# senseBox-Eye_v1_1.net
KiCad netlist of a schematic drawn in EAGLE
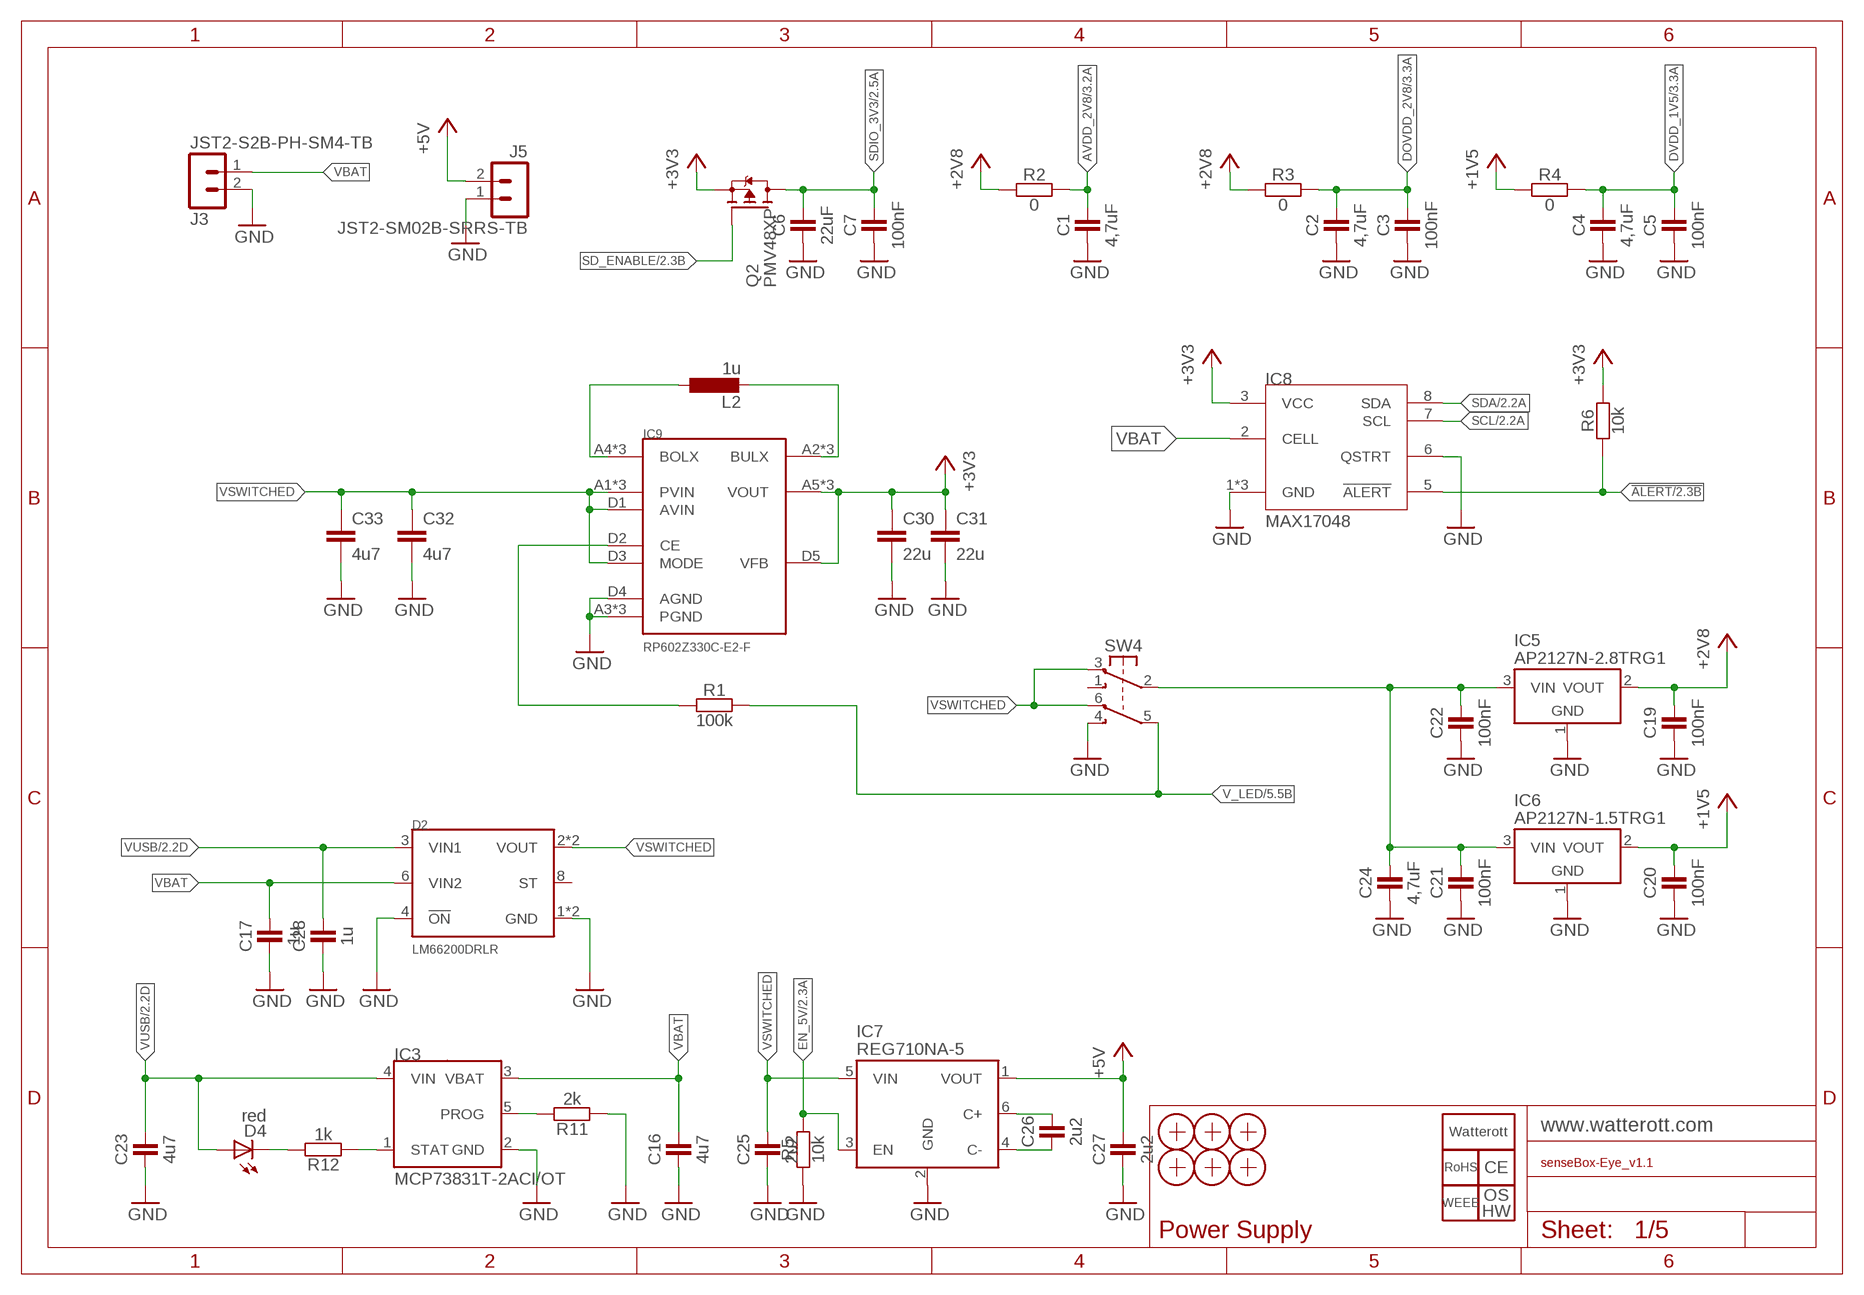
[diagram p0: schematic, sheet 1]
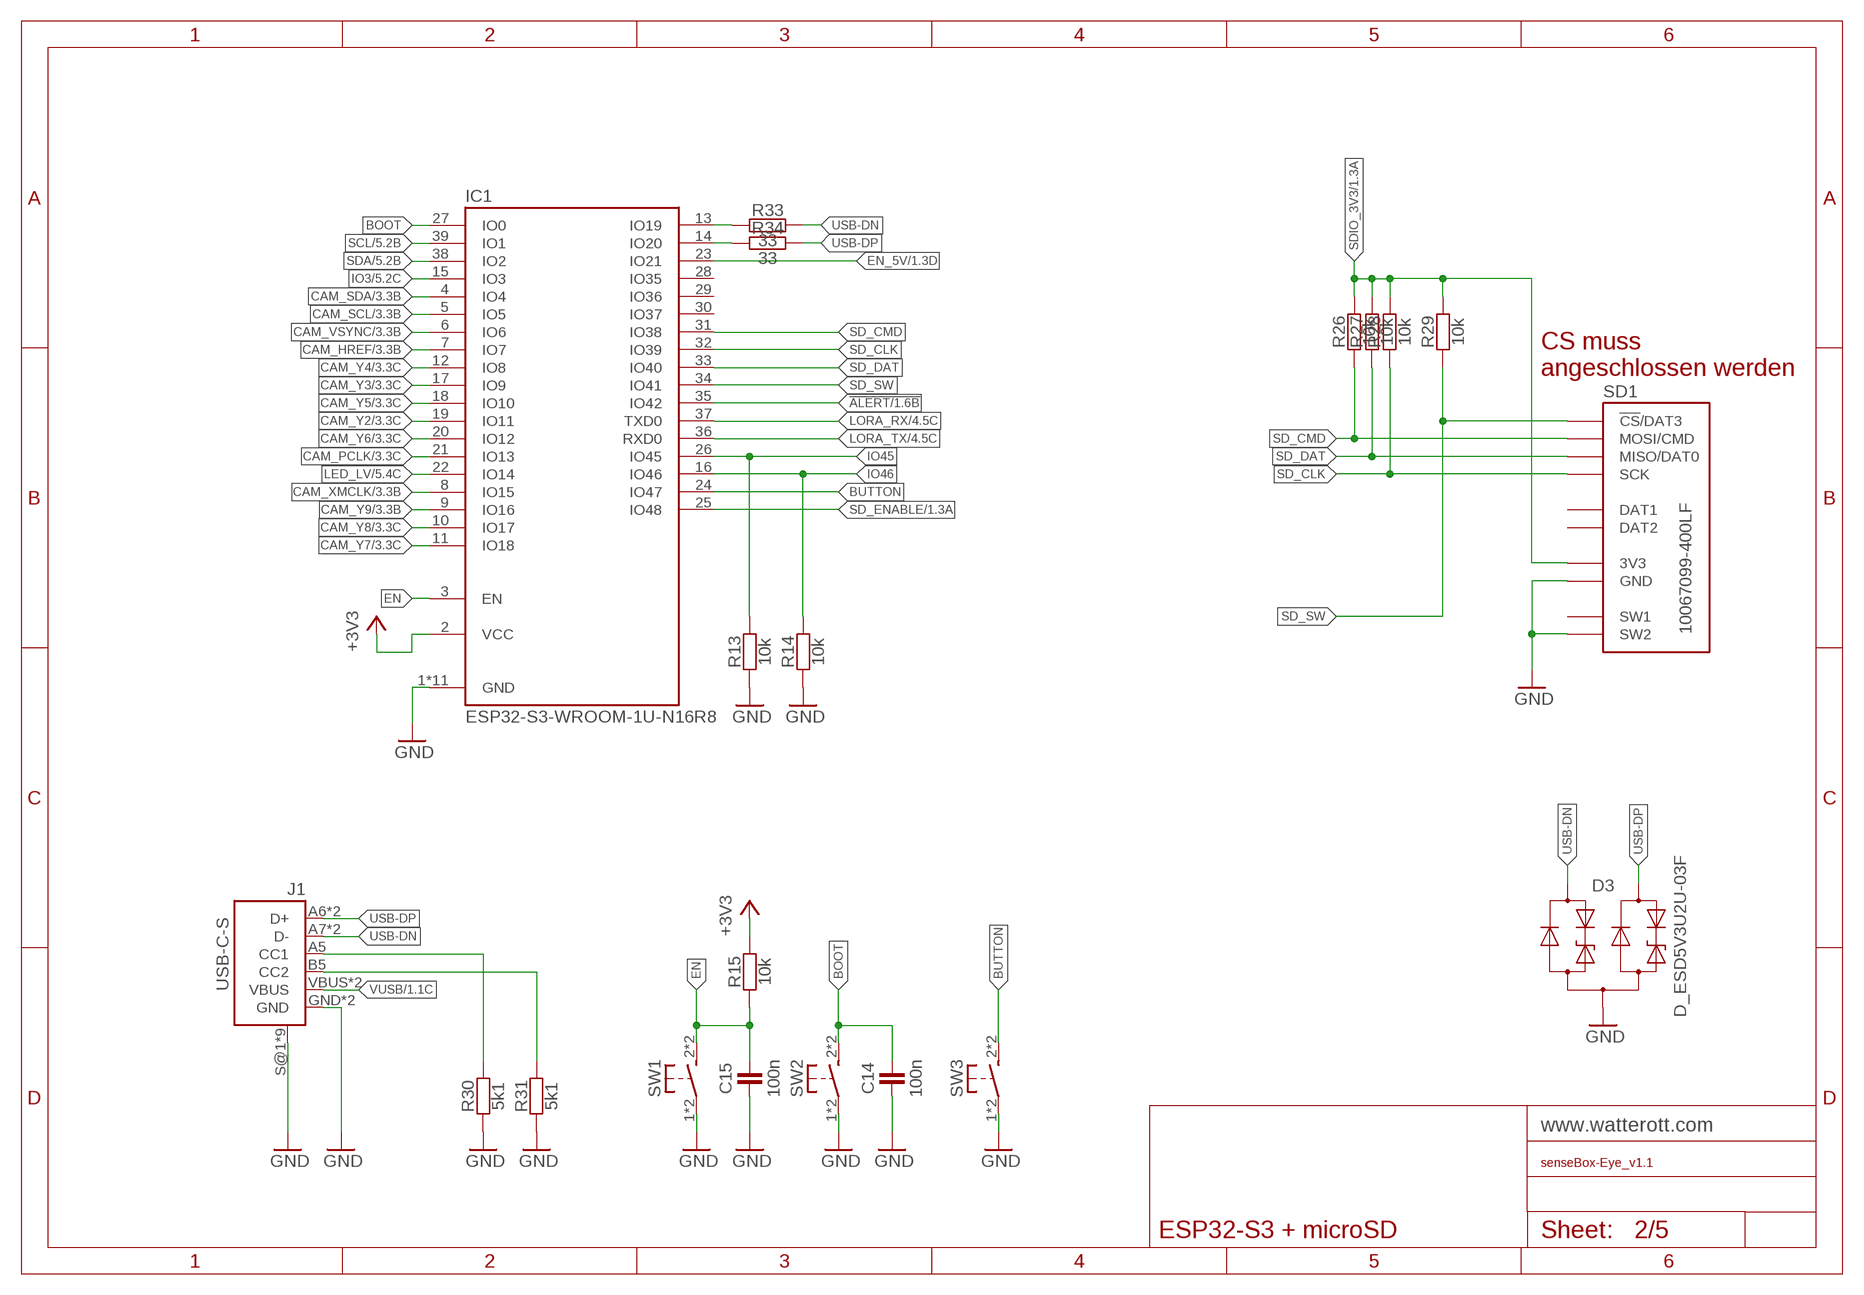
[diagram p1: schematic, sheet 2]
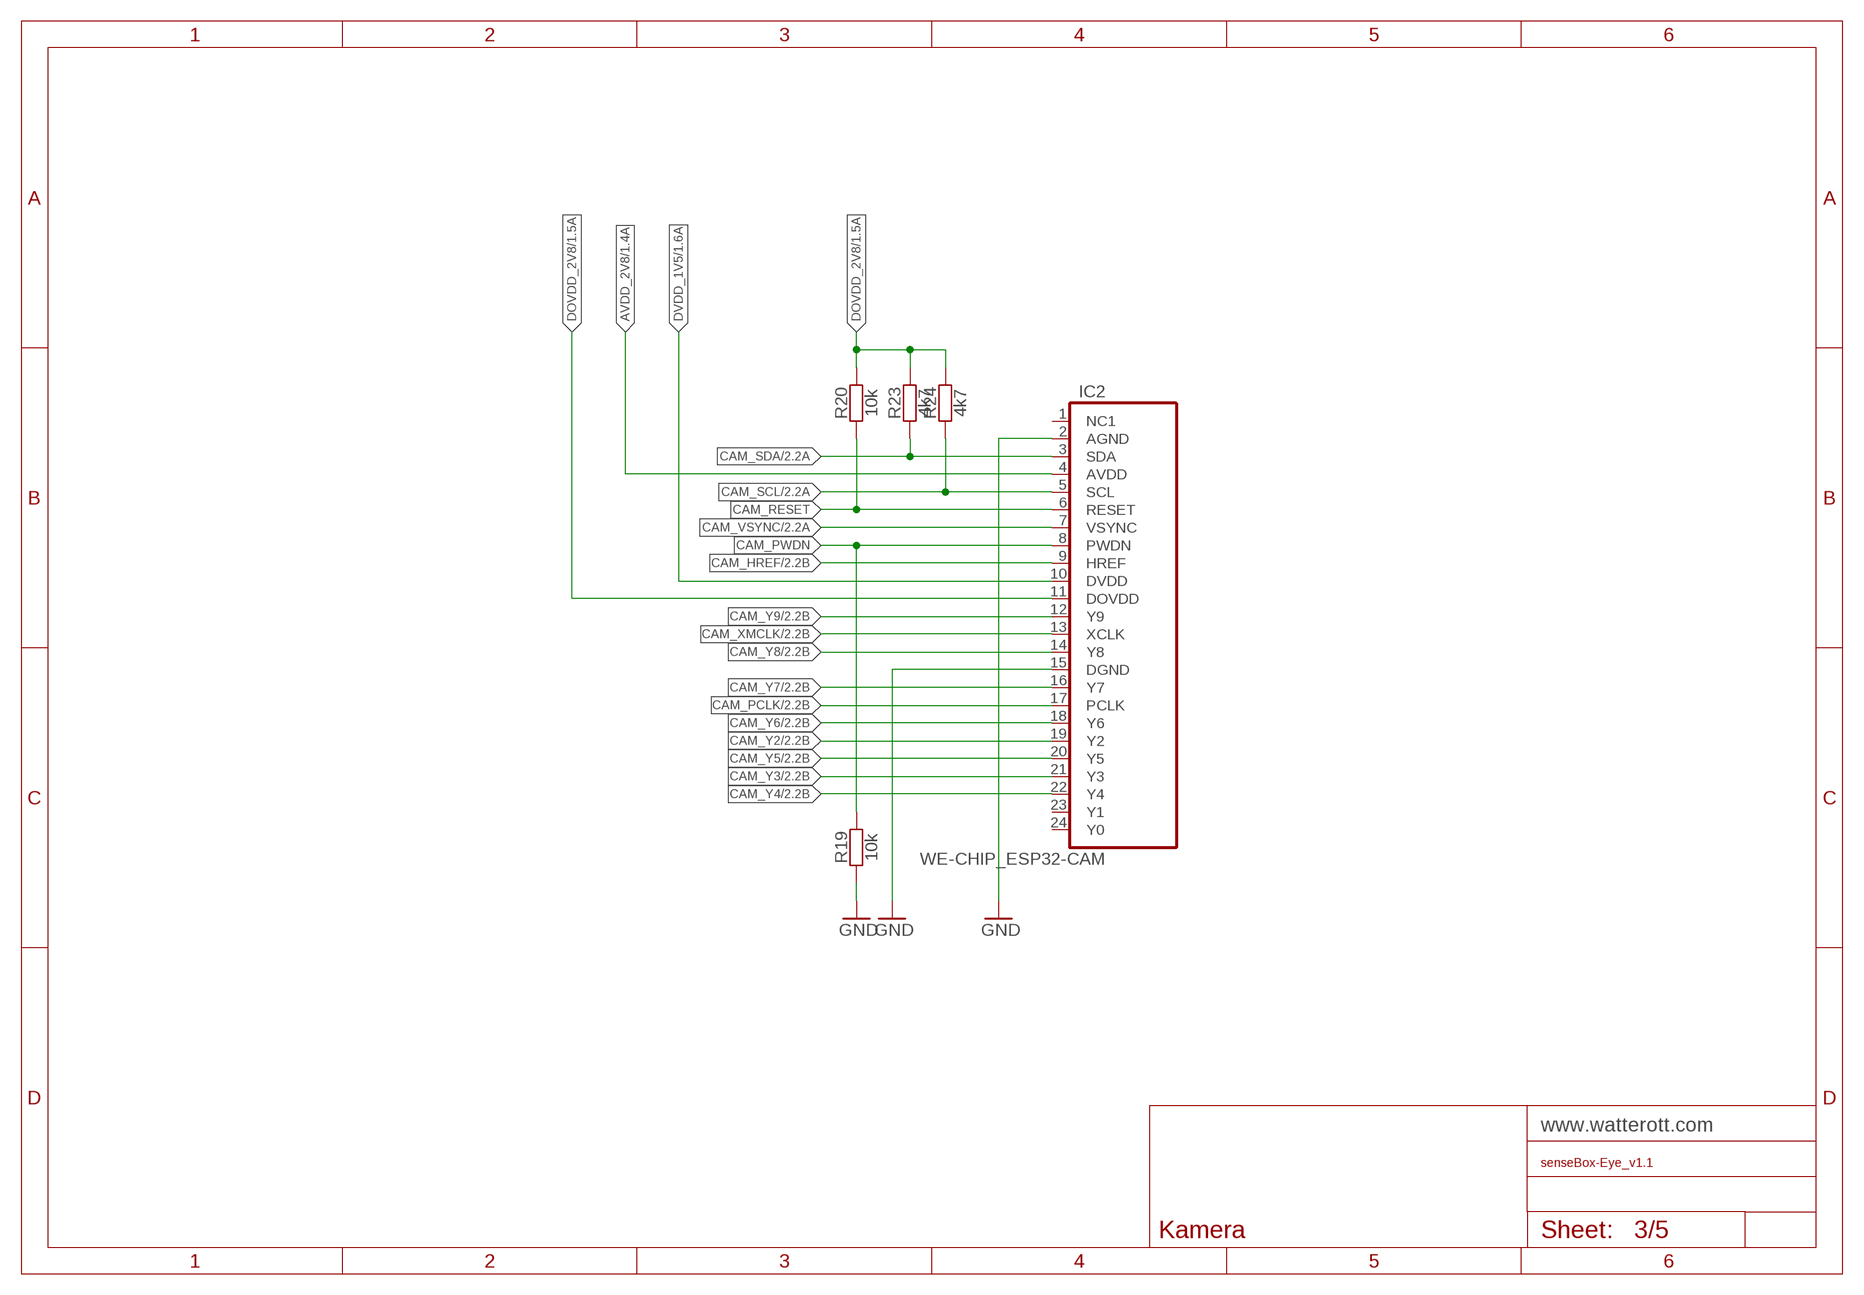
[diagram p2: schematic, sheet 3]
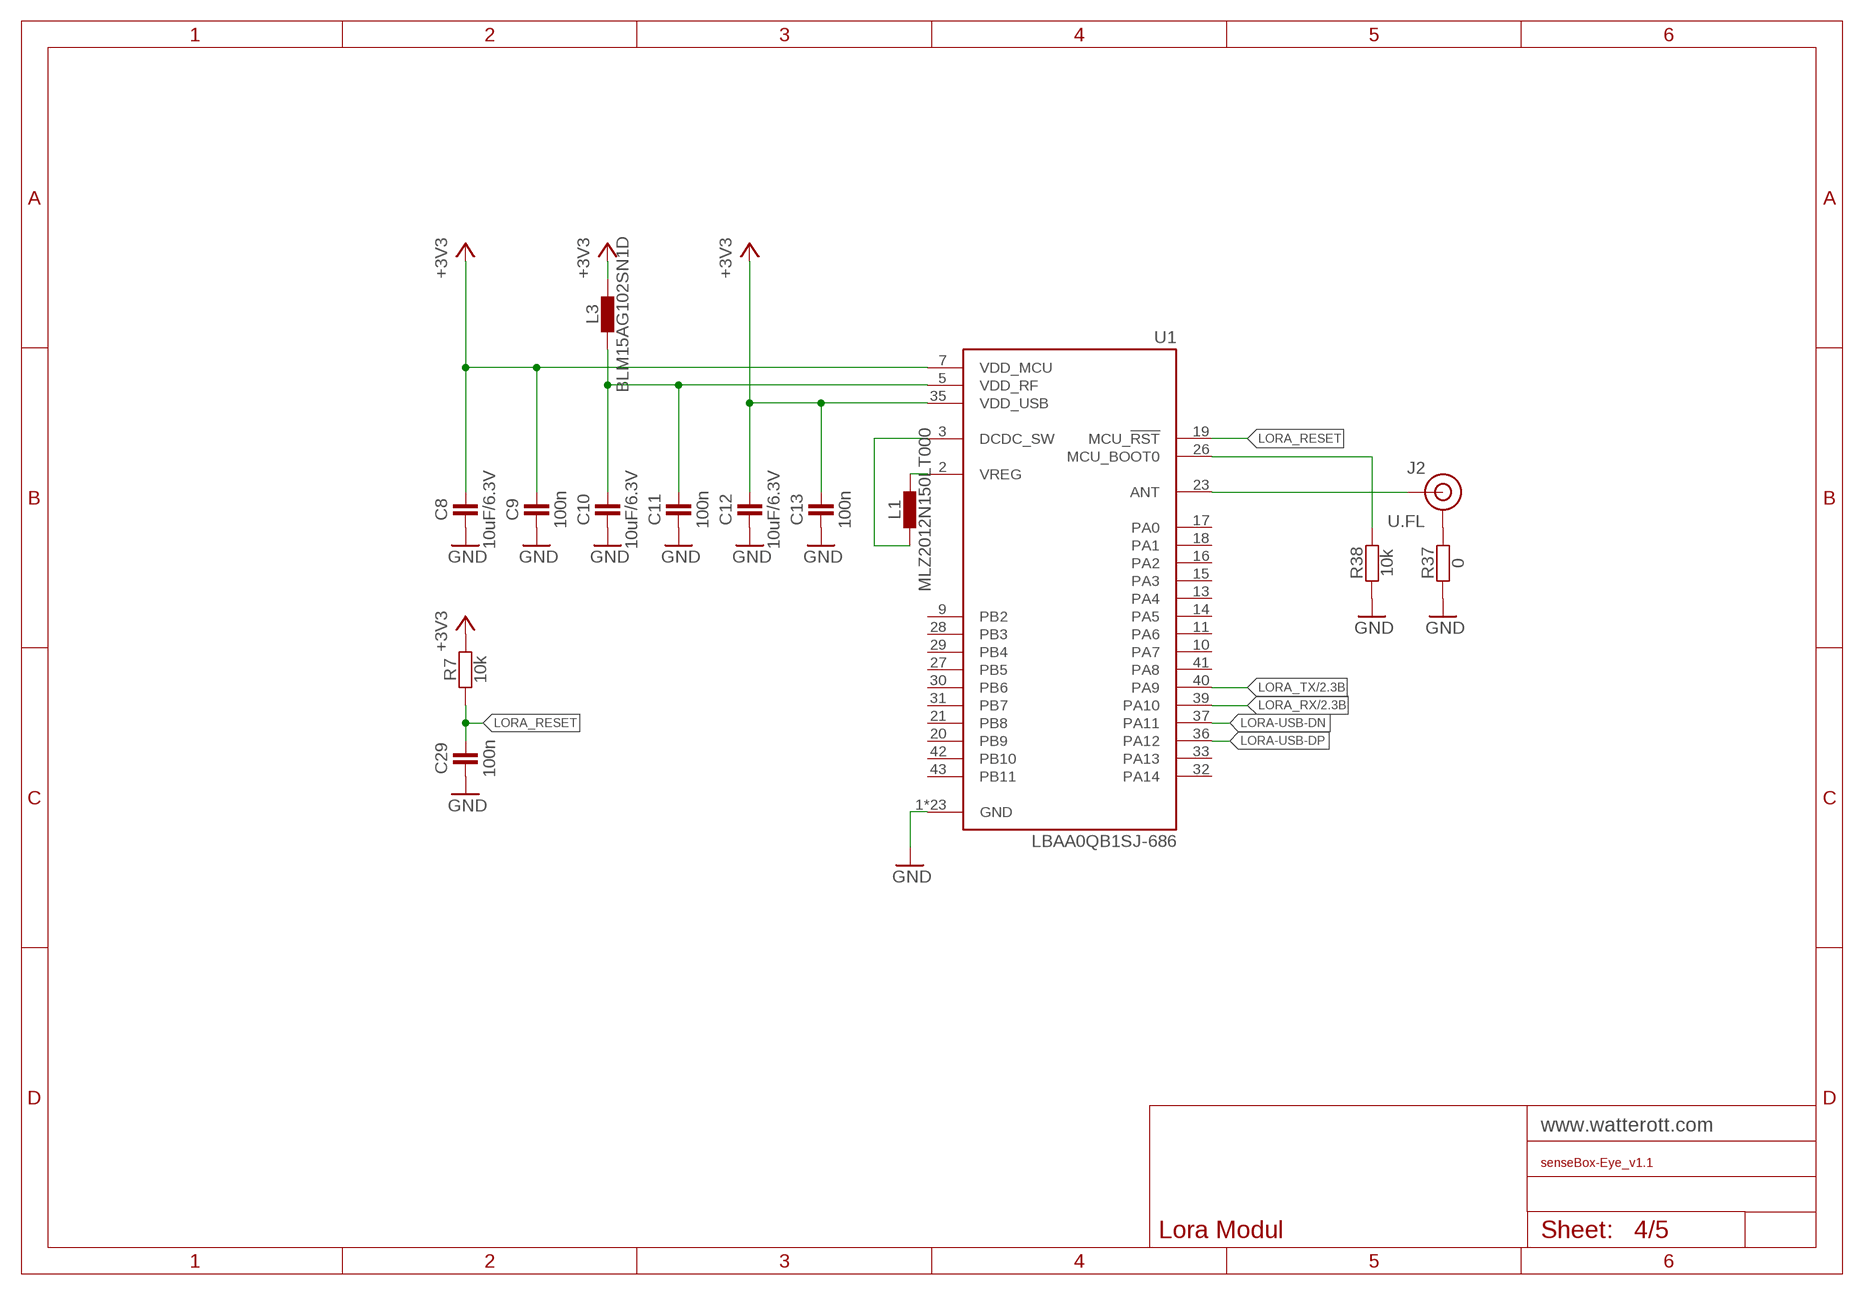
[diagram p3: schematic, sheet 4]
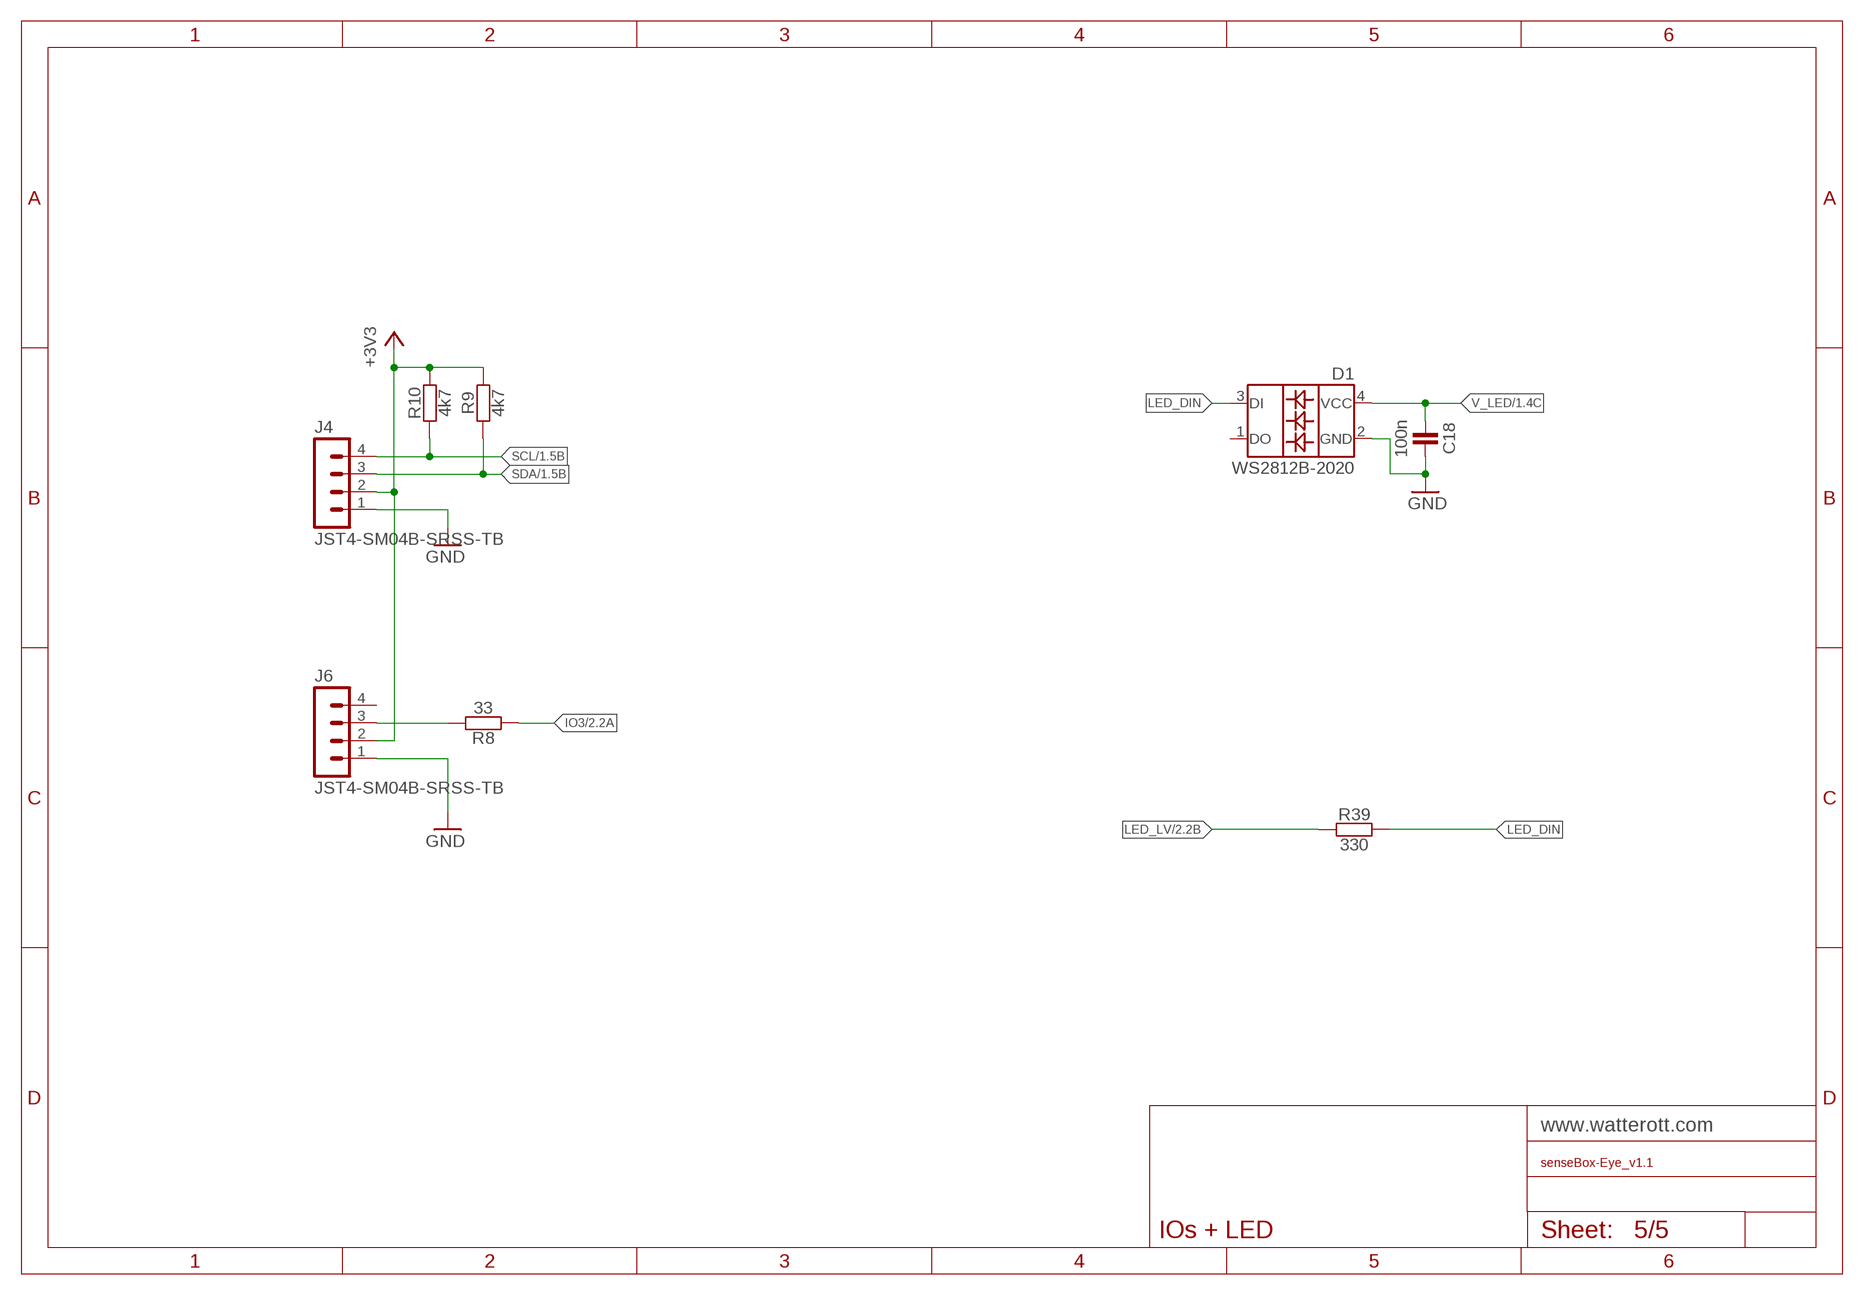
[diagram p4: schematic, sheet 5]

(export (version "E")
  (design (tool "Eeschema 10.0.6"))
  (components
    (comp (ref "C14")
      (value "100n")
      (footprint "eagle-import:C0402")
      (libsource (lib "eagle-import") (part "CAPACITOR-0402"))
    )
    (comp (ref "C15")
      (value "100n")
      (footprint "eagle-import:C0402")
      (libsource (lib "eagle-import") (part "CAPACITOR-0402"))
    )
    (comp (ref "D3")
      (value "D_ESD5V3U2U-03F")
      (footprint "eagle-import:SOT723")
      (libsource (lib "eagle-import") (part "D_ESD5V3U2U-03F"))
    )
    (comp (ref "IC1")
      (value "ESP32-S3-WROOM-1U-N16R8")
      (footprint "eagle-import:ESP32-S3-WROOM-1U")
      (libsource (lib "eagle-import") (part "ESP32_S3-WROOM-1"))
    )
    (comp (ref "J1")
      (value "USB-C-S")
      (footprint "eagle-import:USB-C-S")
      (libsource (lib "eagle-import") (part "USB-C-S"))
    )
    (comp (ref "R13")
      (value "10k")
      (footprint "eagle-import:C0402")
      (libsource (lib "eagle-import") (part "RESISTOR-0402"))
    )
    (comp (ref "R14")
      (value "10k")
      (footprint "eagle-import:C0402")
      (libsource (lib "eagle-import") (part "RESISTOR-0402"))
    )
    (comp (ref "R15")
      (value "10k")
      (footprint "eagle-import:C0402")
      (libsource (lib "eagle-import") (part "RESISTOR-0402"))
    )
    (comp (ref "R26")
      (value "10k")
      (footprint "eagle-import:C0402")
      (libsource (lib "eagle-import") (part "RESISTOR-0402"))
    )
    (comp (ref "R27")
      (value "10k")
      (footprint "eagle-import:C0402")
      (libsource (lib "eagle-import") (part "RESISTOR-0402"))
    )
    (comp (ref "R28")
      (value "10k")
      (footprint "eagle-import:C0402")
      (libsource (lib "eagle-import") (part "RESISTOR-0402"))
    )
    (comp (ref "R29")
      (value "10k")
      (footprint "eagle-import:C0402")
      (libsource (lib "eagle-import") (part "RESISTOR-0402"))
    )
    (comp (ref "R30")
      (value "5k1")
      (footprint "eagle-import:C0402")
      (libsource (lib "eagle-import") (part "RESISTOR-0402"))
    )
    (comp (ref "R31")
      (value "5k1")
      (footprint "eagle-import:C0402")
      (libsource (lib "eagle-import") (part "RESISTOR-0402"))
    )
    (comp (ref "R33")
      (value "33")
      (footprint "eagle-import:C0402")
      (libsource (lib "eagle-import") (part "RESISTOR-0402"))
    )
    (comp (ref "R34")
      (value "33")
      (footprint "eagle-import:C0402")
      (libsource (lib "eagle-import") (part "RESISTOR-0402"))
    )
    (comp (ref "SD1")
      (value "10067099-400LF")
      (footprint "eagle-import:SD_47309XXXX")
      (libsource (lib "eagle-import") (part "SD-CARD-MSD47"))
    )
    (comp (ref "SW1")
      (value "SW-TACTILE-TL3305")
      (footprint "eagle-import:TL3305")
      (libsource (lib "eagle-import") (part "SW-TACTILE-TL3305"))
    )
    (comp (ref "SW2")
      (value "SW-TACTILE-TL3305")
      (footprint "eagle-import:TL3305")
      (libsource (lib "eagle-import") (part "SW-TACTILE-TL3305"))
    )
    (comp (ref "SW3")
      (value "SW-TACTILE-TL3305")
      (footprint "eagle-import:TL3305")
      (libsource (lib "eagle-import") (part "SW-TACTILE-TL3305"))
    )
    (comp (ref "C18")
      (value "100n")
      (footprint "eagle-import:C0402")
      (libsource (lib "eagle-import") (part "CAPACITOR-0402"))
    )
    (comp (ref "D1")
      (value "WS2812B-2020")
      (footprint "eagle-import:WS2812_2020")
      (libsource (lib "eagle-import") (part "WS2812B-2020"))
    )
    (comp (ref "J4")
      (value "JST4-SM04B-SRSS-TB")
      (footprint "eagle-import:JST_SM04B-SRSS-TB")
      (libsource (lib "eagle-import") (part "JST4-SM04B-SRSS-TB"))
    )
    (comp (ref "J6")
      (value "JST4-SM04B-SRSS-TB")
      (footprint "eagle-import:JST_SM04B-SRSS-TB")
      (libsource (lib "eagle-import") (part "JST4-SM04B-SRSS-TB"))
    )
    (comp (ref "R8")
      (value "33")
      (footprint "eagle-import:C0402")
      (libsource (lib "eagle-import") (part "RESISTOR-0402"))
    )
    (comp (ref "R9")
      (value "4k7")
      (footprint "eagle-import:C0402")
      (libsource (lib "eagle-import") (part "RESISTOR-0402"))
    )
    (comp (ref "R10")
      (value "4k7")
      (footprint "eagle-import:C0402")
      (libsource (lib "eagle-import") (part "RESISTOR-0402"))
    )
    (comp (ref "R39")
      (value "330")
      (footprint "eagle-import:C0402")
      (libsource (lib "eagle-import") (part "RESISTOR-0402"))
    )
    (comp (ref "IC2")
      (value "WE-CHIP_ESP32-CAM")
      (footprint "eagle-import:WE-CHIP_FPC24-0.5-CAM")
      (libsource (lib "eagle-import") (part "WE-CHIP_ESP32-CAM"))
    )
    (comp (ref "R19")
      (value "10k")
      (footprint "eagle-import:C0402")
      (libsource (lib "eagle-import") (part "RESISTOR-0402"))
    )
    (comp (ref "R20")
      (value "10k")
      (footprint "eagle-import:C0402")
      (libsource (lib "eagle-import") (part "RESISTOR-0402"))
    )
    (comp (ref "R23")
      (value "4k7")
      (footprint "eagle-import:C0402")
      (libsource (lib "eagle-import") (part "RESISTOR-0402"))
    )
    (comp (ref "R24")
      (value "4k7")
      (footprint "eagle-import:C0402")
      (libsource (lib "eagle-import") (part "RESISTOR-0402"))
    )
    (comp (ref "C1")
      (value "4,7uF")
      (footprint "eagle-import:C0402")
      (libsource (lib "eagle-import") (part "CAPACITOR-0402"))
    )
    (comp (ref "C2")
      (value "4,7uF")
      (footprint "eagle-import:C0402")
      (libsource (lib "eagle-import") (part "CAPACITOR-0402"))
    )
    (comp (ref "C3")
      (value "100nF")
      (footprint "eagle-import:C0402")
      (libsource (lib "eagle-import") (part "CAPACITOR-0402"))
    )
    (comp (ref "C4")
      (value "4,7uF")
      (footprint "eagle-import:C0402")
      (libsource (lib "eagle-import") (part "CAPACITOR-0402"))
    )
    (comp (ref "C5")
      (value "100nF")
      (footprint "eagle-import:C0402")
      (libsource (lib "eagle-import") (part "CAPACITOR-0402"))
    )
    (comp (ref "C6")
      (value "22uF")
      (footprint "eagle-import:C0402")
      (libsource (lib "eagle-import") (part "CAPACITOR-0402"))
    )
    (comp (ref "C7")
      (value "100nF")
      (footprint "eagle-import:C0402")
      (libsource (lib "eagle-import") (part "CAPACITOR-0402"))
    )
    (comp (ref "C16")
      (value "4u7")
      (footprint "eagle-import:C0402")
      (libsource (lib "eagle-import") (part "CAPACITOR-0402"))
    )
    (comp (ref "C17")
      (value "1u")
      (footprint "eagle-import:C0402")
      (libsource (lib "eagle-import") (part "CAPACITOR-0402"))
    )
    (comp (ref "C19")
      (value "100nF")
      (footprint "eagle-import:C0402")
      (libsource (lib "eagle-import") (part "CAPACITOR-0402"))
    )
    (comp (ref "C20")
      (value "100nF")
      (footprint "eagle-import:C0402")
      (libsource (lib "eagle-import") (part "CAPACITOR-0402"))
    )
    (comp (ref "C21")
      (value "100nF")
      (footprint "eagle-import:C0402")
      (libsource (lib "eagle-import") (part "CAPACITOR-0402"))
    )
    (comp (ref "C22")
      (value "100nF")
      (footprint "eagle-import:C0402")
      (libsource (lib "eagle-import") (part "CAPACITOR-0402"))
    )
    (comp (ref "C23")
      (value "4u7")
      (footprint "eagle-import:C0402")
      (libsource (lib "eagle-import") (part "CAPACITOR-0402"))
    )
    (comp (ref "C24")
      (value "4,7uF")
      (footprint "eagle-import:C0402")
      (libsource (lib "eagle-import") (part "CAPACITOR-0402"))
    )
    (comp (ref "C25")
      (value "2u2")
      (footprint "eagle-import:C0402")
      (libsource (lib "eagle-import") (part "CAPACITOR-0402"))
    )
    (comp (ref "C26")
      (value "2u2")
      (footprint "eagle-import:C0402")
      (libsource (lib "eagle-import") (part "CAPACITOR-0402"))
    )
    (comp (ref "C27")
      (value "2u2")
      (footprint "eagle-import:C0402")
      (libsource (lib "eagle-import") (part "CAPACITOR-0402"))
    )
    (comp (ref "C28")
      (value "1u")
      (footprint "eagle-import:C0402")
      (libsource (lib "eagle-import") (part "CAPACITOR-0402"))
    )
    (comp (ref "C30")
      (value "22u")
      (footprint "eagle-import:0805N")
      (fields (field (name "VOLTAGE") "6V3"))
      (libsource (lib "eagle-import") (part "C_0805N_22U"))
    )
    (comp (ref "C31")
      (value "22u")
      (footprint "eagle-import:0805N")
      (fields (field (name "VOLTAGE") "6V3"))
      (libsource (lib "eagle-import") (part "C_0805N_22U"))
    )
    (comp (ref "C32")
      (value "4u7")
      (footprint "eagle-import:0603N")
      (fields (field (name "VOLTAGE") "6V3"))
      (libsource (lib "eagle-import") (part "C_0603N_4U7"))
    )
    (comp (ref "C33")
      (value "4u7")
      (footprint "eagle-import:0603N")
      (fields (field (name "VOLTAGE") "6V3"))
      (libsource (lib "eagle-import") (part "C_0603N_4U7"))
    )
    (comp (ref "D2")
      (value "LM66200DRLR")
      (footprint "eagle-import:SOT-5X3")
      (libsource (lib "eagle-import") (part "LM66200"))
    )
    (comp (ref "D4")
      (value "red")
      (footprint "eagle-import:0603N")
      (libsource (lib "eagle-import") (part "LED_0603N_RED"))
    )
    (comp (ref "IC3")
      (value "MCP73831T-2ACI/OT")
      (footprint "eagle-import:SOT23-5")
      (libsource (lib "eagle-import") (part "MCP73831_SOT23-5_MCP73831T-2ACI/OT"))
    )
    (comp (ref "IC5")
      (value "AP2127N-2.8TRG1")
      (footprint "eagle-import:SOT23")
      (libsource (lib "eagle-import") (part "VREG-TS9011-3V3"))
    )
    (comp (ref "IC6")
      (value "AP2127N-1.5TRG1")
      (footprint "eagle-import:SOT23")
      (libsource (lib "eagle-import") (part "VREG-TS9011-3V3"))
    )
    (comp (ref "IC7")
      (value "REG710NA-5")
      (footprint "eagle-import:SOT23-6")
      (libsource (lib "eagle-import") (part "REG710NA-5"))
    )
    (comp (ref "IC8")
      (value "MAX17048")
      (footprint "eagle-import:UDFN8_2020")
      (libsource (lib "eagle-import") (part "MAX1704X"))
    )
    (comp (ref "IC9")
      (value "RP602Z330C-E2-F")
      (footprint "eagle-import:WLCSP-20-P1")
      (libsource (lib "eagle-import") (part "RP602_WLCSP-20-P1_RP602Z330C-E2-F"))
    )
    (comp (ref "J3")
      (value "JST2-S2B-PH-SM4-TB")
      (footprint "eagle-import:JST_S2B-PH-SM4-TB")
      (libsource (lib "eagle-import") (part "JST2-S2B-PH-SM4-TB"))
    )
    (comp (ref "J5")
      (value "JST2-SM02B-SRRS-TB")
      (footprint "eagle-import:JST_SM02B-SRSS-TB")
      (libsource (lib "eagle-import") (part "JST2-SM02B-SRRS-TB"))
    )
    (comp (ref "L2")
      (value "1u")
      (footprint "eagle-import:5040")
      (libsource (lib "eagle-import") (part "L_5040_WE-LQS-1U"))
    )
    (comp (ref "LOGO2")
      (value "LOGO_CE-2")
      (footprint "eagle-import:CE_2MM")
      (libsource (lib "eagle-import") (part "LOGO_CE-2"))
    )
    (comp (ref "LOGO3")
      (value "LOGO_OSHW-2")
      (footprint "eagle-import:OSHW_2MM")
      (libsource (lib "eagle-import") (part "LOGO_OSHW-2"))
    )
    (comp (ref "LOGO4")
      (value "LOGO_ROHS-2")
      (footprint "eagle-import:ROHS_2MM")
      (libsource (lib "eagle-import") (part "LOGO_ROHS-2"))
    )
    (comp (ref "LOGO5")
      (value "LOGO_WEEE-4")
      (footprint "eagle-import:WEEE_4MM")
      (libsource (lib "eagle-import") (part "LOGO_WEEE-4"))
    )
    (comp (ref "LOGO6")
      (value "LOGO_SPARK-2")
      (footprint "eagle-import:SPARK_2MM")
      (libsource (lib "eagle-import") (part "LOGO_SPARK-2"))
    )
    (comp (ref "Q2")
      (value "PMV48XP")
      (footprint "eagle-import:SOT23")
      (fields (field (name "VOLTAGE") "20"))
      (libsource (lib "eagle-import") (part "MOSFET-P_SOT23'_PMV48XP"))
    )
    (comp (ref "R1")
      (value "100k")
      (footprint "eagle-import:C0402")
      (libsource (lib "eagle-import") (part "RESISTOR-0402"))
    )
    (comp (ref "R2")
      (value "0")
      (footprint "eagle-import:C0402")
      (libsource (lib "eagle-import") (part "RESISTOR-0402"))
    )
    (comp (ref "R3")
      (value "0")
      (footprint "eagle-import:C0402")
      (libsource (lib "eagle-import") (part "RESISTOR-0402"))
    )
    (comp (ref "R4")
      (value "0")
      (footprint "eagle-import:C0402")
      (libsource (lib "eagle-import") (part "RESISTOR-0402"))
    )
    (comp (ref "R5")
      (value "10k")
      (footprint "eagle-import:C0402")
      (libsource (lib "eagle-import") (part "RESISTOR-0402"))
    )
    (comp (ref "R6")
      (value "10k")
      (footprint "eagle-import:C0402")
      (libsource (lib "eagle-import") (part "RESISTOR-0402"))
    )
    (comp (ref "R11")
      (value "2k")
      (footprint "eagle-import:C0402")
      (libsource (lib "eagle-import") (part "RESISTOR-0402"))
    )
    (comp (ref "R12")
      (value "1k")
      (footprint "eagle-import:C0402")
      (libsource (lib "eagle-import") (part "RESISTOR-0402"))
    )
    (comp (ref "SW4")
      (value "SW-2UM-CUS22B")
      (footprint "eagle-import:CUS22B")
      (libsource (lib "eagle-import") (part "SW-2UM-CUS22B"))
    )
    (comp (ref "X1")
      (value "PASSER-04")
      (footprint "eagle-import:PASSER_04MM")
      (libsource (lib "eagle-import") (part "PASSER-04"))
    )
    (comp (ref "X2")
      (value "PASSER-04")
      (footprint "eagle-import:PASSER_04MM")
      (libsource (lib "eagle-import") (part "PASSER-04"))
    )
    (comp (ref "X3")
      (value "PASSER-04")
      (footprint "eagle-import:PASSER_04MM")
      (libsource (lib "eagle-import") (part "PASSER-04"))
    )
    (comp (ref "X4")
      (value "PASSER-04")
      (footprint "eagle-import:PASSER_04MM")
      (libsource (lib "eagle-import") (part "PASSER-04"))
    )
    (comp (ref "X5")
      (value "PASSER-04")
      (footprint "eagle-import:PASSER_04MM")
      (libsource (lib "eagle-import") (part "PASSER-04"))
    )
    (comp (ref "X6")
      (value "PASSER-04")
      (footprint "eagle-import:PASSER_04MM")
      (libsource (lib "eagle-import") (part "PASSER-04"))
    )
    (comp (ref "C8")
      (value "10uF/6.3V")
      (footprint "eagle-import:C0402")
      (libsource (lib "eagle-import") (part "CAPACITOR-0402"))
    )
    (comp (ref "C9")
      (value "100n")
      (footprint "eagle-import:C0402")
      (libsource (lib "eagle-import") (part "CAPACITOR-0402"))
    )
    (comp (ref "C10")
      (value "10uF/6.3V")
      (footprint "eagle-import:C0402")
      (libsource (lib "eagle-import") (part "CAPACITOR-0402"))
    )
    (comp (ref "C11")
      (value "100n")
      (footprint "eagle-import:C0402")
      (libsource (lib "eagle-import") (part "CAPACITOR-0402"))
    )
    (comp (ref "C12")
      (value "10uF/6.3V")
      (footprint "eagle-import:C0402")
      (libsource (lib "eagle-import") (part "CAPACITOR-0402"))
    )
    (comp (ref "C13")
      (value "100n")
      (footprint "eagle-import:C0402")
      (libsource (lib "eagle-import") (part "CAPACITOR-0402"))
    )
    (comp (ref "C29")
      (value "100n")
      (footprint "eagle-import:C0402")
      (libsource (lib "eagle-import") (part "CAPACITOR-0402"))
    )
    (comp (ref "J2")
      (value "U.FL")
      (footprint "eagle-import:U.FL")
      (libsource (lib "eagle-import") (part "U.FL"))
    )
    (comp (ref "L1")
      (value "MLZ2012N150LT000")
      (footprint "eagle-import:C0805")
      (libsource (lib "eagle-import") (part "INDUCTOR-0805"))
    )
    (comp (ref "L3")
      (value "BLM15AG102SN1D")
      (footprint "eagle-import:C0402")
      (libsource (lib "eagle-import") (part "INDUCTOR-0402"))
    )
    (comp (ref "R7")
      (value "10k")
      (footprint "eagle-import:C0402")
      (libsource (lib "eagle-import") (part "RESISTOR-0402"))
    )
    (comp (ref "R37")
      (value "0")
      (footprint "eagle-import:C0402")
      (libsource (lib "eagle-import") (part "RESISTOR-0402"))
    )
    (comp (ref "R38")
      (value "10k")
      (footprint "eagle-import:C0402")
      (libsource (lib "eagle-import") (part "RESISTOR-0402"))
    )
    (comp (ref "U1")
      (value "LBAA0QB1SJ-686")
      (footprint "eagle-import:MODULE_LBAA0QB1SJ-296")
      (fields (field (name "MANUFACTURER") "Murata"))
      (libsource (lib "eagle-import") (part "LBAA0QB1SJ-296"))
    )
  )
  (nets
    (net (code "1") (name "+1V5") (class "Default")
      (node (ref "C20") (pin "2") (pinfunction "2_2") (pintype "passive"))
      (node (ref "IC6") (pin "2") (pinfunction "VOUT_2") (pintype "power_in"))
      (node (ref "R4") (pin "1") (pinfunction "1_1") (pintype "passive"))
    )
    (net (code "2") (name "+2V8") (class "Default")
      (node (ref "C19") (pin "2") (pinfunction "2_2") (pintype "passive"))
      (node (ref "IC5") (pin "2") (pinfunction "VOUT_2") (pintype "power_in"))
      (node (ref "R2") (pin "1") (pinfunction "1_1") (pintype "passive"))
      (node (ref "R3") (pin "1") (pinfunction "1_1") (pintype "passive"))
    )
    (net (code "3") (name "+3V3") (class "Default")
      (node (ref "C12") (pin "2") (pinfunction "2_2") (pintype "passive"))
      (node (ref "C13") (pin "2") (pinfunction "2_2") (pintype "passive"))
      (node (ref "C30") (pin "1") (pinfunction "1_1") (pintype "passive"))
      (node (ref "C31") (pin "1") (pinfunction "1_1") (pintype "passive"))
      (node (ref "C8") (pin "2") (pinfunction "2_2") (pintype "passive"))
      (node (ref "C9") (pin "2") (pinfunction "2_2") (pintype "passive"))
      (node (ref "IC1") (pin "2") (pinfunction "VCC_2") (pintype "power_in"))
      (node (ref "IC8") (pin "3") (pinfunction "VCC_3") (pintype "bidirectional"))
      (node (ref "IC9") (pin "A5") (pinfunction "VOUT_A5") (pintype "power_in"))
      (node (ref "IC9") (pin "B5") (pinfunction "VOUT_B5") (pintype "power_in"))
      (node (ref "IC9") (pin "C5") (pinfunction "VOUT_C5") (pintype "power_in"))
      (node (ref "IC9") (pin "D5") (pinfunction "VFB_D5") (pintype "input"))
      (node (ref "J4") (pin "2") (pinfunction "2_2") (pintype "passive"))
      (node (ref "J6") (pin "2") (pinfunction "2_2") (pintype "passive"))
      (node (ref "L3") (pin "2") (pinfunction "2_2") (pintype "passive"))
      (node (ref "Q2") (pin "2") (pinfunction "S_2") (pintype "passive"))
      (node (ref "R10") (pin "1") (pinfunction "1_1") (pintype "passive"))
      (node (ref "R15") (pin "2") (pinfunction "2_2") (pintype "passive"))
      (node (ref "R6") (pin "2") (pinfunction "2_2") (pintype "passive"))
      (node (ref "R7") (pin "2") (pinfunction "2_2") (pintype "passive"))
      (node (ref "R9") (pin "1") (pinfunction "1_1") (pintype "passive"))
      (node (ref "U1") (pin "35") (pinfunction "VDD_USB_35") (pintype "power_in"))
      (node (ref "U1") (pin "7") (pinfunction "VDD_MCU_7") (pintype "power_in"))
    )
    (net (code "4") (name "+5V") (class "Default")
      (node (ref "C27") (pin "2") (pinfunction "2_2") (pintype "passive"))
      (node (ref "IC7") (pin "1") (pinfunction "VOUT_1") (pintype "power_in"))
      (node (ref "J5") (pin "2") (pinfunction "2_2") (pintype "passive"))
    )
    (net (code "5") (name "AVDD_2V8") (class "Default")
      (node (ref "C1") (pin "2") (pinfunction "2_2") (pintype "passive"))
      (node (ref "IC2") (pin "4") (pinfunction "AVDD_4") (pintype "bidirectional"))
      (node (ref "R2") (pin "2") (pinfunction "2_2") (pintype "passive"))
    )
    (net (code "6") (name "BOOT") (class "Default")
      (node (ref "C14") (pin "2") (pinfunction "2_2") (pintype "passive"))
      (node (ref "IC1") (pin "27") (pinfunction "IO0_27") (pintype "bidirectional"))
      (node (ref "SW2") (pin "2") (pinfunction "S1_2") (pintype "passive"))
      (node (ref "SW2") (pin "3") (pinfunction "S1_3") (pintype "passive"))
    )
    (net (code "7") (name "BUTTON") (class "Default")
      (node (ref "IC1") (pin "24") (pinfunction "IO47_24") (pintype "bidirectional"))
      (node (ref "SW3") (pin "2") (pinfunction "S1_2") (pintype "passive"))
      (node (ref "SW3") (pin "3") (pinfunction "S1_3") (pintype "passive"))
    )
    (net (code "8") (name "CAM_HREF") (class "Default")
      (node (ref "IC1") (pin "7") (pinfunction "IO7_7") (pintype "bidirectional"))
      (node (ref "IC2") (pin "9") (pinfunction "HREF_9") (pintype "bidirectional"))
    )
    (net (code "9") (name "CAM_PCLK") (class "Default")
      (node (ref "IC1") (pin "21") (pinfunction "IO13_21") (pintype "bidirectional"))
      (node (ref "IC2") (pin "17") (pinfunction "PCLK_17") (pintype "bidirectional"))
    )
    (net (code "10") (name "CAM_PWDN") (class "Default")
      (node (ref "IC2") (pin "8") (pinfunction "PWDN_8") (pintype "bidirectional"))
      (node (ref "R19") (pin "2") (pinfunction "2_2") (pintype "passive"))
    )
    (net (code "11") (name "CAM_RESET") (class "Default")
      (node (ref "IC2") (pin "6") (pinfunction "RESET_6") (pintype "bidirectional"))
      (node (ref "R20") (pin "1") (pinfunction "1_1") (pintype "passive"))
    )
    (net (code "12") (name "CAM_SCL") (class "Default")
      (node (ref "IC1") (pin "5") (pinfunction "IO5_5") (pintype "bidirectional"))
      (node (ref "IC2") (pin "5") (pinfunction "SCL_5") (pintype "bidirectional"))
      (node (ref "R24") (pin "1") (pinfunction "1_1") (pintype "passive"))
    )
    (net (code "13") (name "CAM_SDA") (class "Default")
      (node (ref "IC1") (pin "4") (pinfunction "IO4_4") (pintype "bidirectional"))
      (node (ref "IC2") (pin "3") (pinfunction "SDA_3") (pintype "bidirectional"))
      (node (ref "R23") (pin "1") (pinfunction "1_1") (pintype "passive"))
    )
    (net (code "14") (name "CAM_VSYNC") (class "Default")
      (node (ref "IC1") (pin "6") (pinfunction "IO6_6") (pintype "bidirectional"))
      (node (ref "IC2") (pin "7") (pinfunction "VSYNC_7") (pintype "bidirectional"))
    )
    (net (code "15") (name "CAM_XMCLK") (class "Default")
      (node (ref "IC1") (pin "8") (pinfunction "IO15_8") (pintype "bidirectional"))
      (node (ref "IC2") (pin "13") (pinfunction "XCLK_13") (pintype "bidirectional"))
    )
    (net (code "16") (name "CAM_Y2") (class "Default")
      (node (ref "IC1") (pin "19") (pinfunction "IO11_19") (pintype "bidirectional"))
      (node (ref "IC2") (pin "19") (pinfunction "Y2_19") (pintype "bidirectional"))
    )
    (net (code "17") (name "CAM_Y3") (class "Default")
      (node (ref "IC1") (pin "17") (pinfunction "IO9_17") (pintype "bidirectional"))
      (node (ref "IC2") (pin "21") (pinfunction "Y3_21") (pintype "bidirectional"))
    )
    (net (code "18") (name "CAM_Y4") (class "Default")
      (node (ref "IC1") (pin "12") (pinfunction "IO8_12") (pintype "bidirectional"))
      (node (ref "IC2") (pin "22") (pinfunction "Y4_22") (pintype "bidirectional"))
    )
    (net (code "19") (name "CAM_Y5") (class "Default")
      (node (ref "IC1") (pin "18") (pinfunction "IO10_18") (pintype "bidirectional"))
      (node (ref "IC2") (pin "20") (pinfunction "Y5_20") (pintype "bidirectional"))
    )
    (net (code "20") (name "CAM_Y6") (class "Default")
      (node (ref "IC1") (pin "20") (pinfunction "IO12_20") (pintype "bidirectional"))
      (node (ref "IC2") (pin "18") (pinfunction "Y6_18") (pintype "bidirectional"))
    )
    (net (code "21") (name "CAM_Y7") (class "Default")
      (node (ref "IC1") (pin "11") (pinfunction "IO18_11") (pintype "bidirectional"))
      (node (ref "IC2") (pin "16") (pinfunction "Y7_16") (pintype "bidirectional"))
    )
    (net (code "22") (name "CAM_Y8") (class "Default")
      (node (ref "IC1") (pin "10") (pinfunction "IO17_10") (pintype "bidirectional"))
      (node (ref "IC2") (pin "14") (pinfunction "Y8_14") (pintype "bidirectional"))
    )
    (net (code "23") (name "CAM_Y9") (class "Default")
      (node (ref "IC1") (pin "9") (pinfunction "IO16_9") (pintype "bidirectional"))
      (node (ref "IC2") (pin "12") (pinfunction "Y9_12") (pintype "bidirectional"))
    )
    (net (code "24") (name "DOVDD_2V8") (class "Default")
      (node (ref "C2") (pin "2") (pinfunction "2_2") (pintype "passive"))
      (node (ref "C3") (pin "2") (pinfunction "2_2") (pintype "passive"))
      (node (ref "IC2") (pin "11") (pinfunction "DOVDD_11") (pintype "bidirectional"))
      (node (ref "R20") (pin "2") (pinfunction "2_2") (pintype "passive"))
      (node (ref "R23") (pin "2") (pinfunction "2_2") (pintype "passive"))
      (node (ref "R24") (pin "2") (pinfunction "2_2") (pintype "passive"))
      (node (ref "R3") (pin "2") (pinfunction "2_2") (pintype "passive"))
    )
    (net (code "25") (name "DVDD_1V5") (class "Default")
      (node (ref "C4") (pin "2") (pinfunction "2_2") (pintype "passive"))
      (node (ref "C5") (pin "2") (pinfunction "2_2") (pintype "passive"))
      (node (ref "IC2") (pin "10") (pinfunction "DVDD_10") (pintype "bidirectional"))
      (node (ref "R4") (pin "2") (pinfunction "2_2") (pintype "passive"))
    )
    (net (code "26") (name "EN") (class "Default")
      (node (ref "C15") (pin "2") (pinfunction "2_2") (pintype "passive"))
      (node (ref "IC1") (pin "3") (pinfunction "EN_3") (pintype "bidirectional"))
      (node (ref "R15") (pin "1") (pinfunction "1_1") (pintype "passive"))
      (node (ref "SW1") (pin "2") (pinfunction "S1_2") (pintype "passive"))
      (node (ref "SW1") (pin "3") (pinfunction "S1_3") (pintype "passive"))
    )
    (net (code "27") (name "EN_5V") (class "Default")
      (node (ref "IC1") (pin "23") (pinfunction "IO21_23") (pintype "bidirectional"))
      (node (ref "IC7") (pin "3") (pinfunction "EN_3") (pintype "passive"))
      (node (ref "R5") (pin "2") (pinfunction "2_2") (pintype "passive"))
    )
    (net (code "28") (name "GND") (class "Default")
      (node (ref "C1") (pin "1") (pinfunction "1_1") (pintype "passive"))
      (node (ref "C10") (pin "1") (pinfunction "1_1") (pintype "passive"))
      (node (ref "C11") (pin "1") (pinfunction "1_1") (pintype "passive"))
      (node (ref "C12") (pin "1") (pinfunction "1_1") (pintype "passive"))
      (node (ref "C13") (pin "1") (pinfunction "1_1") (pintype "passive"))
      (node (ref "C14") (pin "1") (pinfunction "1_1") (pintype "passive"))
      (node (ref "C15") (pin "1") (pinfunction "1_1") (pintype "passive"))
      (node (ref "C16") (pin "1") (pinfunction "1_1") (pintype "passive"))
      (node (ref "C17") (pin "1") (pinfunction "1_1") (pintype "passive"))
      (node (ref "C18") (pin "1") (pinfunction "1_1") (pintype "passive"))
      (node (ref "C19") (pin "1") (pinfunction "1_1") (pintype "passive"))
      (node (ref "C2") (pin "1") (pinfunction "1_1") (pintype "passive"))
      (node (ref "C20") (pin "1") (pinfunction "1_1") (pintype "passive"))
      (node (ref "C21") (pin "1") (pinfunction "1_1") (pintype "passive"))
      (node (ref "C22") (pin "1") (pinfunction "1_1") (pintype "passive"))
      (node (ref "C23") (pin "1") (pinfunction "1_1") (pintype "passive"))
      (node (ref "C24") (pin "1") (pinfunction "1_1") (pintype "passive"))
      (node (ref "C25") (pin "1") (pinfunction "1_1") (pintype "passive"))
      (node (ref "C27") (pin "1") (pinfunction "1_1") (pintype "passive"))
      (node (ref "C28") (pin "1") (pinfunction "1_1") (pintype "passive"))
      (node (ref "C29") (pin "1") (pinfunction "1_1") (pintype "passive"))
      (node (ref "C3") (pin "1") (pinfunction "1_1") (pintype "passive"))
      (node (ref "C30") (pin "2") (pinfunction "2_2") (pintype "passive"))
      (node (ref "C31") (pin "2") (pinfunction "2_2") (pintype "passive"))
      (node (ref "C32") (pin "2") (pinfunction "2_2") (pintype "passive"))
      (node (ref "C33") (pin "2") (pinfunction "2_2") (pintype "passive"))
      (node (ref "C4") (pin "1") (pinfunction "1_1") (pintype "passive"))
      (node (ref "C5") (pin "1") (pinfunction "1_1") (pintype "passive"))
      (node (ref "C6") (pin "1") (pinfunction "1_1") (pintype "passive"))
      (node (ref "C7") (pin "1") (pinfunction "1_1") (pintype "passive"))
      (node (ref "C8") (pin "1") (pinfunction "1_1") (pintype "passive"))
      (node (ref "C9") (pin "1") (pinfunction "1_1") (pintype "passive"))
      (node (ref "D1") (pin "2") (pinfunction "GND_2") (pintype "power_in"))
      (node (ref "D2") (pin "1") (pinfunction "GND_1") (pintype "power_in"))
      (node (ref "D2") (pin "4") (pinfunction "~{ON}_4") (pintype "input"))
      (node (ref "D2") (pin "5") (pinfunction "GND_5") (pintype "power_in"))
      (node (ref "D3") (pin "3") (pinfunction "A_3") (pintype "passive"))
      (node (ref "IC1") (pin "1") (pinfunction "GND_1") (pintype "power_in"))
      (node (ref "IC1") (pin "40") (pinfunction "GND_40") (pintype "power_in"))
      (node (ref "IC1") (pin "P$1") (pinfunction "GND_P$1") (pintype "power_in"))
      (node (ref "IC1") (pin "P$2") (pinfunction "GND_P$2") (pintype "power_in"))
      (node (ref "IC1") (pin "P$3") (pinfunction "GND_P$3") (pintype "power_in"))
      (node (ref "IC1") (pin "P$4") (pinfunction "GND_P$4") (pintype "power_in"))
      (node (ref "IC1") (pin "P$5") (pinfunction "GND_P$5") (pintype "power_in"))
      (node (ref "IC1") (pin "P$6") (pinfunction "GND_P$6") (pintype "power_in"))
      (node (ref "IC1") (pin "P$7") (pinfunction "GND_P$7") (pintype "power_in"))
      (node (ref "IC1") (pin "P$8") (pinfunction "GND_P$8") (pintype "power_in"))
      (node (ref "IC1") (pin "P$9") (pinfunction "GND_P$9") (pintype "power_in"))
      (node (ref "IC2") (pin "15") (pinfunction "DGND_15") (pintype "bidirectional"))
      (node (ref "IC2") (pin "2") (pinfunction "AGND_2") (pintype "bidirectional"))
      (node (ref "IC3") (pin "2") (pinfunction "GND_2") (pintype "power_in"))
      (node (ref "IC5") (pin "1") (pinfunction "GND_1") (pintype "power_in"))
      (node (ref "IC6") (pin "1") (pinfunction "GND_1") (pintype "power_in"))
      (node (ref "IC7") (pin "2") (pinfunction "GND_2") (pintype "power_in"))
      (node (ref "IC8") (pin "1") (pinfunction "GND_1") (pintype "bidirectional"))
      (node (ref "IC8") (pin "4") (pinfunction "GND_4") (pintype "bidirectional"))
      (node (ref "IC8") (pin "6") (pinfunction "QSTRT_6") (pintype "bidirectional"))
      (node (ref "IC8") (pin "TP") (pinfunction "GND_TP") (pintype "bidirectional"))
      (node (ref "IC9") (pin "A3") (pinfunction "PGND_A3") (pintype "power_in"))
      (node (ref "IC9") (pin "B3") (pinfunction "PGND_B3") (pintype "power_in"))
      (node (ref "IC9") (pin "C3") (pinfunction "PGND_C3") (pintype "power_in"))
      (node (ref "IC9") (pin "D4") (pinfunction "AGND_D4") (pintype "power_in"))
      (node (ref "J1") (pin "GND") (pinfunction "GND_GND") (pintype "power_in"))
      (node (ref "J1") (pin "GND2") (pinfunction "GND_GND2") (pintype "power_in"))
      (node (ref "J1") (pin "S@1") (pinfunction "SHIELD_S@1") (pintype "passive"))
      (node (ref "J1") (pin "S@2") (pinfunction "SHIELD_S@2") (pintype "passive"))
      (node (ref "J1") (pin "S@3") (pinfunction "SHIELD_S@3") (pintype "passive"))
      (node (ref "J1") (pin "S@4") (pinfunction "SHIELD_S@4") (pintype "passive"))
      (node (ref "J1") (pin "S@5") (pinfunction "SHIELD_S@5") (pintype "passive"))
      (node (ref "J1") (pin "S@6") (pinfunction "SHIELD_S@6") (pintype "passive"))
      (node (ref "J1") (pin "S@7") (pinfunction "SHIELD_S@7") (pintype "passive"))
      (node (ref "J1") (pin "S@8") (pinfunction "SHIELD_S@8") (pintype "passive"))
      (node (ref "J1") (pin "S@9") (pinfunction "SHIELD_S@9") (pintype "passive"))
      (node (ref "J3") (pin "2") (pinfunction "2_2") (pintype "passive"))
      (node (ref "J4") (pin "1") (pinfunction "1_1") (pintype "passive"))
      (node (ref "J5") (pin "1") (pinfunction "1_1") (pintype "passive"))
      (node (ref "J6") (pin "1") (pinfunction "1_1") (pintype "passive"))
      (node (ref "R11") (pin "1") (pinfunction "1_1") (pintype "passive"))
      (node (ref "R13") (pin "1") (pinfunction "1_1") (pintype "passive"))
      (node (ref "R14") (pin "1") (pinfunction "1_1") (pintype "passive"))
      (node (ref "R19") (pin "1") (pinfunction "1_1") (pintype "passive"))
      (node (ref "R30") (pin "1") (pinfunction "1_1") (pintype "passive"))
      (node (ref "R31") (pin "1") (pinfunction "1_1") (pintype "passive"))
      (node (ref "R37") (pin "1") (pinfunction "1_1") (pintype "passive"))
      (node (ref "R38") (pin "1") (pinfunction "1_1") (pintype "passive"))
      (node (ref "R5") (pin "1") (pinfunction "1_1") (pintype "passive"))
      (node (ref "SD1") (pin "GND") (pinfunction "GND_GND") (pintype "bidirectional"))
      (node (ref "SD1") (pin "GND@1") (pinfunction "GND_GND@1") (pintype "bidirectional"))
      (node (ref "SD1") (pin "GND@2") (pinfunction "GND_GND@2") (pintype "bidirectional"))
      (node (ref "SD1") (pin "SW2") (pinfunction "SW2_SW2") (pintype "bidirectional"))
      (node (ref "SW1") (pin "1") (pinfunction "P1_1") (pintype "passive"))
      (node (ref "SW1") (pin "4") (pinfunction "P1_4") (pintype "passive"))
      (node (ref "SW2") (pin "1") (pinfunction "P1_1") (pintype "passive"))
      (node (ref "SW2") (pin "4") (pinfunction "P1_4") (pintype "passive"))
      (node (ref "SW3") (pin "1") (pinfunction "P1_1") (pintype "passive"))
      (node (ref "SW3") (pin "4") (pinfunction "P1_4") (pintype "passive"))
      (node (ref "SW4") (pin "4") (pinfunction "NO2_4") (pintype "passive"))
      (node (ref "U1") (pin "1") (pinfunction "GND_1") (pintype "power_in"))
      (node (ref "U1") (pin "12") (pinfunction "GND_12") (pintype "power_in"))
      (node (ref "U1") (pin "22") (pinfunction "GND_22") (pintype "power_in"))
      (node (ref "U1") (pin "24") (pinfunction "GND_24") (pintype "power_in"))
      (node (ref "U1") (pin "25") (pinfunction "GND_25") (pintype "power_in"))
      (node (ref "U1") (pin "34") (pinfunction "GND_34") (pintype "power_in"))
      (node (ref "U1") (pin "38") (pinfunction "GND_38") (pintype "power_in"))
      (node (ref "U1") (pin "4") (pinfunction "GND_4") (pintype "power_in"))
      (node (ref "U1") (pin "44") (pinfunction "GND_44") (pintype "power_in"))
      (node (ref "U1") (pin "45") (pinfunction "GND_45") (pintype "power_in"))
      (node (ref "U1") (pin "46") (pinfunction "GND_46") (pintype "power_in"))
      (node (ref "U1") (pin "47") (pinfunction "GND_47") (pintype "power_in"))
      (node (ref "U1") (pin "48") (pinfunction "GND_48") (pintype "power_in"))
      (node (ref "U1") (pin "49") (pinfunction "GND_49") (pintype "power_in"))
      (node (ref "U1") (pin "50") (pinfunction "GND_50") (pintype "power_in"))
      (node (ref "U1") (pin "51") (pinfunction "GND_51") (pintype "power_in"))
      (node (ref "U1") (pin "52") (pinfunction "GND_52") (pintype "power_in"))
      (node (ref "U1") (pin "53") (pinfunction "GND_53") (pintype "power_in"))
      (node (ref "U1") (pin "54") (pinfunction "GND_54") (pintype "power_in"))
      (node (ref "U1") (pin "55") (pinfunction "GND_55") (pintype "power_in"))
      (node (ref "U1") (pin "56") (pinfunction "GND_56") (pintype "power_in"))
      (node (ref "U1") (pin "6") (pinfunction "GND_6") (pintype "power_in"))
      (node (ref "U1") (pin "8") (pinfunction "GND_8") (pintype "power_in"))
    )
    (net (code "29") (name "IO3") (class "Default")
      (node (ref "IC1") (pin "15") (pinfunction "IO3_15") (pintype "bidirectional"))
      (node (ref "R8") (pin "2") (pinfunction "2_2") (pintype "passive"))
    )
    (net (code "30") (name "IO45") (class "Default")
      (node (ref "IC1") (pin "26") (pinfunction "IO45_26") (pintype "bidirectional"))
      (node (ref "R13") (pin "2") (pinfunction "2_2") (pintype "passive"))
    )
    (net (code "31") (name "IO46") (class "Default")
      (node (ref "IC1") (pin "16") (pinfunction "IO46_16") (pintype "bidirectional"))
      (node (ref "R14") (pin "2") (pinfunction "2_2") (pintype "passive"))
    )
    (net (code "32") (name "LED_DIN") (class "Default")
      (node (ref "D1") (pin "3") (pinfunction "DI_3") (pintype "bidirectional"))
      (node (ref "R39") (pin "2") (pinfunction "2_2") (pintype "passive"))
    )
    (net (code "33") (name "LED_LV") (class "Default")
      (node (ref "IC1") (pin "22") (pinfunction "IO14_22") (pintype "bidirectional"))
      (node (ref "R39") (pin "1") (pinfunction "1_1") (pintype "passive"))
    )
    (net (code "34") (name "LORA-USB-DN") (class "Default")
      (node (ref "U1") (pin "37") (pinfunction "PA11_37") (pintype "bidirectional"))
    )
    (net (code "35") (name "LORA-USB-DP") (class "Default")
      (node (ref "U1") (pin "36") (pinfunction "PA12_36") (pintype "bidirectional"))
    )
    (net (code "36") (name "LORA_RESET") (class "Default")
      (node (ref "C29") (pin "2") (pinfunction "2_2") (pintype "passive"))
      (node (ref "R7") (pin "1") (pinfunction "1_1") (pintype "passive"))
      (node (ref "U1") (pin "19") (pinfunction "MCU_~{RST}_19") (pintype "input"))
    )
    (net (code "37") (name "LORA_RX") (class "Default")
      (node (ref "IC1") (pin "37") (pinfunction "TXD0_37") (pintype "bidirectional"))
      (node (ref "U1") (pin "39") (pinfunction "PA10_39") (pintype "bidirectional"))
    )
    (net (code "38") (name "LORA_TX") (class "Default")
      (node (ref "IC1") (pin "36") (pinfunction "RXD0_36") (pintype "bidirectional"))
      (node (ref "U1") (pin "40") (pinfunction "PA9_40") (pintype "bidirectional"))
    )
    (net (code "39") (name "Net-(D4-PadC)") (class "Default")
      (node (ref "D4") (pin "C") (pinfunction "C_C") (pintype "passive"))
      (node (ref "R12") (pin "2") (pinfunction "2_2") (pintype "passive"))
    )
    (net (code "40") (name "Net-(IC1-IO19)") (class "Default")
      (node (ref "IC1") (pin "13") (pinfunction "IO19_13") (pintype "bidirectional"))
      (node (ref "R33") (pin "1") (pinfunction "1_1") (pintype "passive"))
    )
    (net (code "41") (name "Net-(IC1-IO20)") (class "Default")
      (node (ref "IC1") (pin "14") (pinfunction "IO20_14") (pintype "bidirectional"))
      (node (ref "R34") (pin "1") (pinfunction "1_1") (pintype "passive"))
    )
    (net (code "42") (name "Net-(IC3-PROG)") (class "Default")
      (node (ref "IC3") (pin "5") (pinfunction "PROG_5") (pintype "input"))
      (node (ref "R11") (pin "2") (pinfunction "2_2") (pintype "passive"))
    )
    (net (code "43") (name "Net-(IC3-STAT)") (class "Default")
      (node (ref "IC3") (pin "1") (pinfunction "STAT_1") (pintype "open_collector"))
      (node (ref "R12") (pin "1") (pinfunction "1_1") (pintype "passive"))
    )
    (net (code "44") (name "Net-(IC5-VIN)") (class "Default")
      (node (ref "C21") (pin "2") (pinfunction "2_2") (pintype "passive"))
      (node (ref "C22") (pin "2") (pinfunction "2_2") (pintype "passive"))
      (node (ref "C24") (pin "2") (pinfunction "2_2") (pintype "passive"))
      (node (ref "IC5") (pin "3") (pinfunction "VIN_3") (pintype "power_in"))
      (node (ref "IC6") (pin "3") (pinfunction "VIN_3") (pintype "power_in"))
      (node (ref "SW4") (pin "2") (pinfunction "C1_2") (pintype "passive"))
    )
    (net (code "45") (name "Net-(IC7-C+)") (class "Default")
      (node (ref "C26") (pin "2") (pinfunction "2_2") (pintype "passive"))
      (node (ref "IC7") (pin "6") (pinfunction "C+_6") (pintype "passive"))
    )
    (net (code "46") (name "Net-(IC7-C-)") (class "Default")
      (node (ref "C26") (pin "1") (pinfunction "1_1") (pintype "passive"))
      (node (ref "IC7") (pin "4") (pinfunction "C-_4") (pintype "passive"))
    )
    (net (code "47") (name "Net-(IC9-BOLX-PadA4)") (class "Default")
      (node (ref "IC9") (pin "A4") (pinfunction "BOLX_A4") (pintype "output"))
      (node (ref "IC9") (pin "B4") (pinfunction "BOLX_B4") (pintype "output"))
      (node (ref "IC9") (pin "C4") (pinfunction "BOLX_C4") (pintype "output"))
      (node (ref "L2") (pin "1") (pinfunction "1_1") (pintype "passive"))
    )
    (net (code "48") (name "Net-(IC9-BULX-PadA2)") (class "Default")
      (node (ref "IC9") (pin "A2") (pinfunction "BULX_A2") (pintype "output"))
      (node (ref "IC9") (pin "B2") (pinfunction "BULX_B2") (pintype "output"))
      (node (ref "IC9") (pin "C2") (pinfunction "BULX_C2") (pintype "output"))
      (node (ref "L2") (pin "2") (pinfunction "2_2") (pintype "passive"))
    )
    (net (code "49") (name "Net-(IC9-CE)") (class "Default")
      (node (ref "IC9") (pin "D2") (pinfunction "CE_D2") (pintype "input"))
      (node (ref "R1") (pin "1") (pinfunction "1_1") (pintype "passive"))
    )
    (net (code "50") (name "Net-(J1-CC1)") (class "Default")
      (node (ref "J1") (pin "A5") (pinfunction "CC1_A5") (pintype "bidirectional"))
      (node (ref "R30") (pin "2") (pinfunction "2_2") (pintype "passive"))
    )
    (net (code "51") (name "Net-(J1-CC2)") (class "Default")
      (node (ref "J1") (pin "B5") (pinfunction "CC2_B5") (pintype "bidirectional"))
      (node (ref "R31") (pin "2") (pinfunction "2_2") (pintype "passive"))
    )
    (net (code "52") (name "Net-(J2-GND-Pad1)") (class "Default")
      (node (ref "J2") (pin "1") (pinfunction "GND_1") (pintype "bidirectional"))
      (node (ref "J2") (pin "2") (pinfunction "GND_2") (pintype "bidirectional"))
      (node (ref "R37") (pin "2") (pinfunction "2_2") (pintype "passive"))
    )
    (net (code "53") (name "Net-(J2-SIGNAL)") (class "Default")
      (node (ref "J2") (pin "FEED") (pinfunction "SIGNAL_FEED") (pintype "bidirectional"))
      (node (ref "U1") (pin "23") (pinfunction "ANT_23") (pintype "bidirectional"))
    )
    (net (code "54") (name "Net-(J6-Pad3)") (class "Default")
      (node (ref "J6") (pin "3") (pinfunction "3_3") (pintype "passive"))
      (node (ref "R8") (pin "1") (pinfunction "1_1") (pintype "passive"))
    )
    (net (code "55") (name "Net-(U1-DCDC_SW)") (class "Default")
      (node (ref "L1") (pin "2") (pinfunction "2_2") (pintype "passive"))
      (node (ref "U1") (pin "3") (pinfunction "DCDC_SW_3") (pintype "output"))
    )
    (net (code "56") (name "Net-(U1-MCU_BOOT0)") (class "Default")
      (node (ref "R38") (pin "2") (pinfunction "2_2") (pintype "passive"))
      (node (ref "U1") (pin "26") (pinfunction "MCU_BOOT0_26") (pintype "input"))
    )
    (net (code "57") (name "Net-(U1-VDD_RF)") (class "Default")
      (node (ref "C10") (pin "2") (pinfunction "2_2") (pintype "passive"))
      (node (ref "C11") (pin "2") (pinfunction "2_2") (pintype "passive"))
      (node (ref "L3") (pin "1") (pinfunction "1_1") (pintype "passive"))
      (node (ref "U1") (pin "5") (pinfunction "VDD_RF_5") (pintype "power_in"))
    )
    (net (code "58") (name "Net-(U1-VREG)") (class "Default")
      (node (ref "L1") (pin "1") (pinfunction "1_1") (pintype "passive"))
      (node (ref "U1") (pin "2") (pinfunction "VREG_2") (pintype "output"))
    )
    (net (code "59") (name "SCL") (class "Default")
      (node (ref "IC1") (pin "39") (pinfunction "IO1_39") (pintype "bidirectional"))
      (node (ref "IC8") (pin "7") (pinfunction "SCL_7") (pintype "bidirectional"))
      (node (ref "J4") (pin "4") (pinfunction "4_4") (pintype "passive"))
      (node (ref "R10") (pin "2") (pinfunction "2_2") (pintype "passive"))
    )
    (net (code "60") (name "SDA") (class "Default")
      (node (ref "IC1") (pin "38") (pinfunction "IO2_38") (pintype "bidirectional"))
      (node (ref "IC8") (pin "8") (pinfunction "SDA_8") (pintype "bidirectional"))
      (node (ref "J4") (pin "3") (pinfunction "3_3") (pintype "passive"))
      (node (ref "R9") (pin "2") (pinfunction "2_2") (pintype "passive"))
    )
    (net (code "61") (name "SDIO_3V3") (class "Default")
      (node (ref "C6") (pin "2") (pinfunction "2_2") (pintype "passive"))
      (node (ref "C7") (pin "2") (pinfunction "2_2") (pintype "passive"))
      (node (ref "Q2") (pin "3") (pinfunction "D_3") (pintype "passive"))
      (node (ref "R26") (pin "2") (pinfunction "2_2") (pintype "passive"))
      (node (ref "R27") (pin "2") (pinfunction "2_2") (pintype "passive"))
      (node (ref "R28") (pin "2") (pinfunction "2_2") (pintype "passive"))
      (node (ref "R29") (pin "2") (pinfunction "2_2") (pintype "passive"))
      (node (ref "SD1") (pin "VCC") (pinfunction "3V3_VCC") (pintype "bidirectional"))
    )
    (net (code "62") (name "SD_CLK") (class "Default")
      (node (ref "IC1") (pin "32") (pinfunction "IO39_32") (pintype "bidirectional"))
      (node (ref "R28") (pin "1") (pinfunction "1_1") (pintype "passive"))
      (node (ref "SD1") (pin "SCK") (pinfunction "SCK_SCK") (pintype "bidirectional"))
    )
    (net (code "63") (name "SD_CMD") (class "Default")
      (node (ref "IC1") (pin "31") (pinfunction "IO38_31") (pintype "bidirectional"))
      (node (ref "R26") (pin "1") (pinfunction "1_1") (pintype "passive"))
      (node (ref "SD1") (pin "MOSI") (pinfunction "MOSI/CMD_MOSI") (pintype "bidirectional"))
    )
    (net (code "64") (name "SD_DAT") (class "Default")
      (node (ref "IC1") (pin "33") (pinfunction "IO40_33") (pintype "bidirectional"))
      (node (ref "R27") (pin "1") (pinfunction "1_1") (pintype "passive"))
      (node (ref "SD1") (pin "MISO") (pinfunction "MISO/DAT0_MISO") (pintype "bidirectional"))
    )
    (net (code "65") (name "SD_ENABLE") (class "Default")
      (node (ref "IC1") (pin "25") (pinfunction "IO48_25") (pintype "bidirectional"))
      (node (ref "Q2") (pin "1") (pinfunction "G_1") (pintype "passive"))
    )
    (net (code "66") (name "SD_SW") (class "Default")
      (node (ref "IC1") (pin "34") (pinfunction "IO41_34") (pintype "bidirectional"))
      (node (ref "R29") (pin "1") (pinfunction "1_1") (pintype "passive"))
      (node (ref "SD1") (pin "CS") (pinfunction "~{CS}/DAT3_CS") (pintype "bidirectional"))
    )
    (net (code "67") (name "USB-DN") (class "Default")
      (node (ref "D3") (pin "1") (pinfunction "C1_1") (pintype "passive"))
      (node (ref "J1") (pin "A7") (pinfunction "D-_A7") (pintype "bidirectional"))
      (node (ref "J1") (pin "B7") (pinfunction "D-_B7") (pintype "bidirectional"))
      (node (ref "R33") (pin "2") (pinfunction "2_2") (pintype "passive"))
    )
    (net (code "68") (name "USB-DP") (class "Default")
      (node (ref "D3") (pin "2") (pinfunction "C2_2") (pintype "passive"))
      (node (ref "J1") (pin "A6") (pinfunction "D+_A6") (pintype "bidirectional"))
      (node (ref "J1") (pin "B6") (pinfunction "D+_B6") (pintype "bidirectional"))
      (node (ref "R34") (pin "2") (pinfunction "2_2") (pintype "passive"))
    )
    (net (code "69") (name "VBAT") (class "Default")
      (node (ref "C16") (pin "2") (pinfunction "2_2") (pintype "passive"))
      (node (ref "C17") (pin "2") (pinfunction "2_2") (pintype "passive"))
      (node (ref "D2") (pin "6") (pinfunction "VIN2_6") (pintype "power_in"))
      (node (ref "IC3") (pin "3") (pinfunction "VBAT_3") (pintype "bidirectional"))
      (node (ref "IC8") (pin "2") (pinfunction "CELL_2") (pintype "bidirectional"))
      (node (ref "J3") (pin "1") (pinfunction "1_1") (pintype "passive"))
    )
    (net (code "70") (name "VSWITCHED") (class "Default")
      (node (ref "C25") (pin "2") (pinfunction "2_2") (pintype "passive"))
      (node (ref "C32") (pin "1") (pinfunction "1_1") (pintype "passive"))
      (node (ref "C33") (pin "1") (pinfunction "1_1") (pintype "passive"))
      (node (ref "D2") (pin "2") (pinfunction "VOUT_2") (pintype "power_in"))
      (node (ref "D2") (pin "7") (pinfunction "VOUT_7") (pintype "power_in"))
      (node (ref "IC7") (pin "5") (pinfunction "VIN_5") (pintype "power_in"))
      (node (ref "IC9") (pin "A1") (pinfunction "PVIN_A1") (pintype "power_in"))
      (node (ref "IC9") (pin "B1") (pinfunction "PVIN_B1") (pintype "power_in"))
      (node (ref "IC9") (pin "C1") (pinfunction "PVIN_C1") (pintype "power_in"))
      (node (ref "IC9") (pin "D1") (pinfunction "AVIN_D1") (pintype "power_in"))
      (node (ref "IC9") (pin "D3") (pinfunction "MODE_D3") (pintype "input"))
      (node (ref "SW4") (pin "3") (pinfunction "NC1_3") (pintype "passive"))
      (node (ref "SW4") (pin "6") (pinfunction "NC2_6") (pintype "passive"))
    )
    (net (code "71") (name "VUSB") (class "Default")
      (node (ref "C23") (pin "2") (pinfunction "2_2") (pintype "passive"))
      (node (ref "C28") (pin "2") (pinfunction "2_2") (pintype "passive"))
      (node (ref "D2") (pin "3") (pinfunction "VIN1_3") (pintype "power_in"))
      (node (ref "D4") (pin "A") (pinfunction "A_A") (pintype "passive"))
      (node (ref "IC3") (pin "4") (pinfunction "VIN_4") (pintype "power_in"))
      (node (ref "J1") (pin "VBUS") (pinfunction "VBUS_VBUS") (pintype "power_in"))
      (node (ref "J1") (pin "VBUS2") (pinfunction "VBUS_VBUS2") (pintype "power_in"))
    )
    (net (code "72") (name "V_LED") (class "Default")
      (node (ref "C18") (pin "2") (pinfunction "2_2") (pintype "passive"))
      (node (ref "D1") (pin "4") (pinfunction "VCC_4") (pintype "power_in"))
      (node (ref "R1") (pin "2") (pinfunction "2_2") (pintype "passive"))
      (node (ref "SW4") (pin "5") (pinfunction "C2_5") (pintype "passive"))
    )
    (net (code "73") (name "unconnected-(D1-DO-Pad1)") (class "Default")
      (node (ref "D1") (pin "1") (pinfunction "DO_1") (pintype "bidirectional"))
    )
    (net (code "74") (name "unconnected-(D2-ST-Pad8)") (class "Default")
      (node (ref "D2") (pin "8") (pinfunction "ST_8") (pintype "open_collector"))
    )
    (net (code "75") (name "unconnected-(IC1-IO35-Pad28)") (class "Default")
      (node (ref "IC1") (pin "28") (pinfunction "IO35_28") (pintype "bidirectional"))
    )
    (net (code "76") (name "unconnected-(IC1-IO36-Pad29)") (class "Default")
      (node (ref "IC1") (pin "29") (pinfunction "IO36_29") (pintype "bidirectional"))
    )
    (net (code "77") (name "unconnected-(IC1-IO37-Pad30)") (class "Default")
      (node (ref "IC1") (pin "30") (pinfunction "IO37_30") (pintype "bidirectional"))
    )
    (net (code "78") (name "unconnected-(IC2-NC1-Pad1)") (class "Default")
      (node (ref "IC2") (pin "1") (pinfunction "NC1_1") (pintype "bidirectional"))
    )
    (net (code "79") (name "unconnected-(IC2-Y0-Pad24)") (class "Default")
      (node (ref "IC2") (pin "24") (pinfunction "Y0_24") (pintype "bidirectional"))
    )
    (net (code "80") (name "unconnected-(IC2-Y1-Pad23)") (class "Default")
      (node (ref "IC2") (pin "23") (pinfunction "Y1_23") (pintype "bidirectional"))
    )
    (net (code "81") (name "unconnected-(J6-Pad4)") (class "Default")
      (node (ref "J6") (pin "4") (pinfunction "4_4") (pintype "passive"))
    )
    (net (code "82") (name "unconnected-(SD1-PadDAT1)") (class "Default")
      (node (ref "SD1") (pin "DAT1") (pinfunction "DAT1_DAT1") (pintype "bidirectional"))
    )
    (net (code "83") (name "unconnected-(SD1-PadDAT2)") (class "Default")
      (node (ref "SD1") (pin "DAT2") (pinfunction "DAT2_DAT2") (pintype "bidirectional"))
    )
    (net (code "84") (name "unconnected-(SD1-PadSW1)") (class "Default")
      (node (ref "SD1") (pin "SW1") (pinfunction "SW1_SW1") (pintype "bidirectional"))
    )
    (net (code "85") (name "unconnected-(SW4-NO1-Pad1)") (class "Default")
      (node (ref "SW4") (pin "1") (pinfunction "NO1_1") (pintype "passive"))
    )
    (net (code "86") (name "unconnected-(U1-PA0-Pad17)") (class "Default")
      (node (ref "U1") (pin "17") (pinfunction "PA0_17") (pintype "bidirectional"))
    )
    (net (code "87") (name "unconnected-(U1-PA1-Pad18)") (class "Default")
      (node (ref "U1") (pin "18") (pinfunction "PA1_18") (pintype "bidirectional"))
    )
    (net (code "88") (name "unconnected-(U1-PA2-Pad16)") (class "Default")
      (node (ref "U1") (pin "16") (pinfunction "PA2_16") (pintype "bidirectional"))
    )
    (net (code "89") (name "unconnected-(U1-PA3-Pad15)") (class "Default")
      (node (ref "U1") (pin "15") (pinfunction "PA3_15") (pintype "bidirectional"))
    )
    (net (code "90") (name "unconnected-(U1-PA4-Pad13)") (class "Default")
      (node (ref "U1") (pin "13") (pinfunction "PA4_13") (pintype "bidirectional"))
    )
    (net (code "91") (name "unconnected-(U1-PA5-Pad14)") (class "Default")
      (node (ref "U1") (pin "14") (pinfunction "PA5_14") (pintype "bidirectional"))
    )
    (net (code "92") (name "unconnected-(U1-PA6-Pad11)") (class "Default")
      (node (ref "U1") (pin "11") (pinfunction "PA6_11") (pintype "bidirectional"))
    )
    (net (code "93") (name "unconnected-(U1-PA7-Pad10)") (class "Default")
      (node (ref "U1") (pin "10") (pinfunction "PA7_10") (pintype "bidirectional"))
    )
    (net (code "94") (name "unconnected-(U1-PA8-Pad41)") (class "Default")
      (node (ref "U1") (pin "41") (pinfunction "PA8_41") (pintype "bidirectional"))
    )
    (net (code "95") (name "unconnected-(U1-PA13-Pad33)") (class "Default")
      (node (ref "U1") (pin "33") (pinfunction "PA13_33") (pintype "bidirectional"))
    )
    (net (code "96") (name "unconnected-(U1-PA14-Pad32)") (class "Default")
      (node (ref "U1") (pin "32") (pinfunction "PA14_32") (pintype "bidirectional"))
    )
    (net (code "97") (name "unconnected-(U1-PB2-Pad9)") (class "Default")
      (node (ref "U1") (pin "9") (pinfunction "PB2_9") (pintype "bidirectional"))
    )
    (net (code "98") (name "unconnected-(U1-PB3-Pad28)") (class "Default")
      (node (ref "U1") (pin "28") (pinfunction "PB3_28") (pintype "bidirectional"))
    )
    (net (code "99") (name "unconnected-(U1-PB4-Pad29)") (class "Default")
      (node (ref "U1") (pin "29") (pinfunction "PB4_29") (pintype "bidirectional"))
    )
    (net (code "100") (name "unconnected-(U1-PB5-Pad27)") (class "Default")
      (node (ref "U1") (pin "27") (pinfunction "PB5_27") (pintype "bidirectional"))
    )
    (net (code "101") (name "unconnected-(U1-PB6-Pad30)") (class "Default")
      (node (ref "U1") (pin "30") (pinfunction "PB6_30") (pintype "bidirectional"))
    )
    (net (code "102") (name "unconnected-(U1-PB7-Pad31)") (class "Default")
      (node (ref "U1") (pin "31") (pinfunction "PB7_31") (pintype "bidirectional"))
    )
    (net (code "103") (name "unconnected-(U1-PB8-Pad21)") (class "Default")
      (node (ref "U1") (pin "21") (pinfunction "PB8_21") (pintype "bidirectional"))
    )
    (net (code "104") (name "unconnected-(U1-PB9-Pad20)") (class "Default")
      (node (ref "U1") (pin "20") (pinfunction "PB9_20") (pintype "bidirectional"))
    )
    (net (code "105") (name "unconnected-(U1-PB10-Pad42)") (class "Default")
      (node (ref "U1") (pin "42") (pinfunction "PB10_42") (pintype "bidirectional"))
    )
    (net (code "106") (name "unconnected-(U1-PB11-Pad43)") (class "Default")
      (node (ref "U1") (pin "43") (pinfunction "PB11_43") (pintype "bidirectional"))
    )
    (net (code "107") (name "~{ALERT}") (class "Default")
      (node (ref "IC1") (pin "35") (pinfunction "IO42_35") (pintype "bidirectional"))
      (node (ref "IC8") (pin "5") (pinfunction "~{ALERT}_5") (pintype "bidirectional"))
      (node (ref "R6") (pin "1") (pinfunction "1_1") (pintype "passive"))
    )
  )
)
